# Stepper_Motor_Driver.net
KiCad netlist of a schematic drawn in Altium Designer
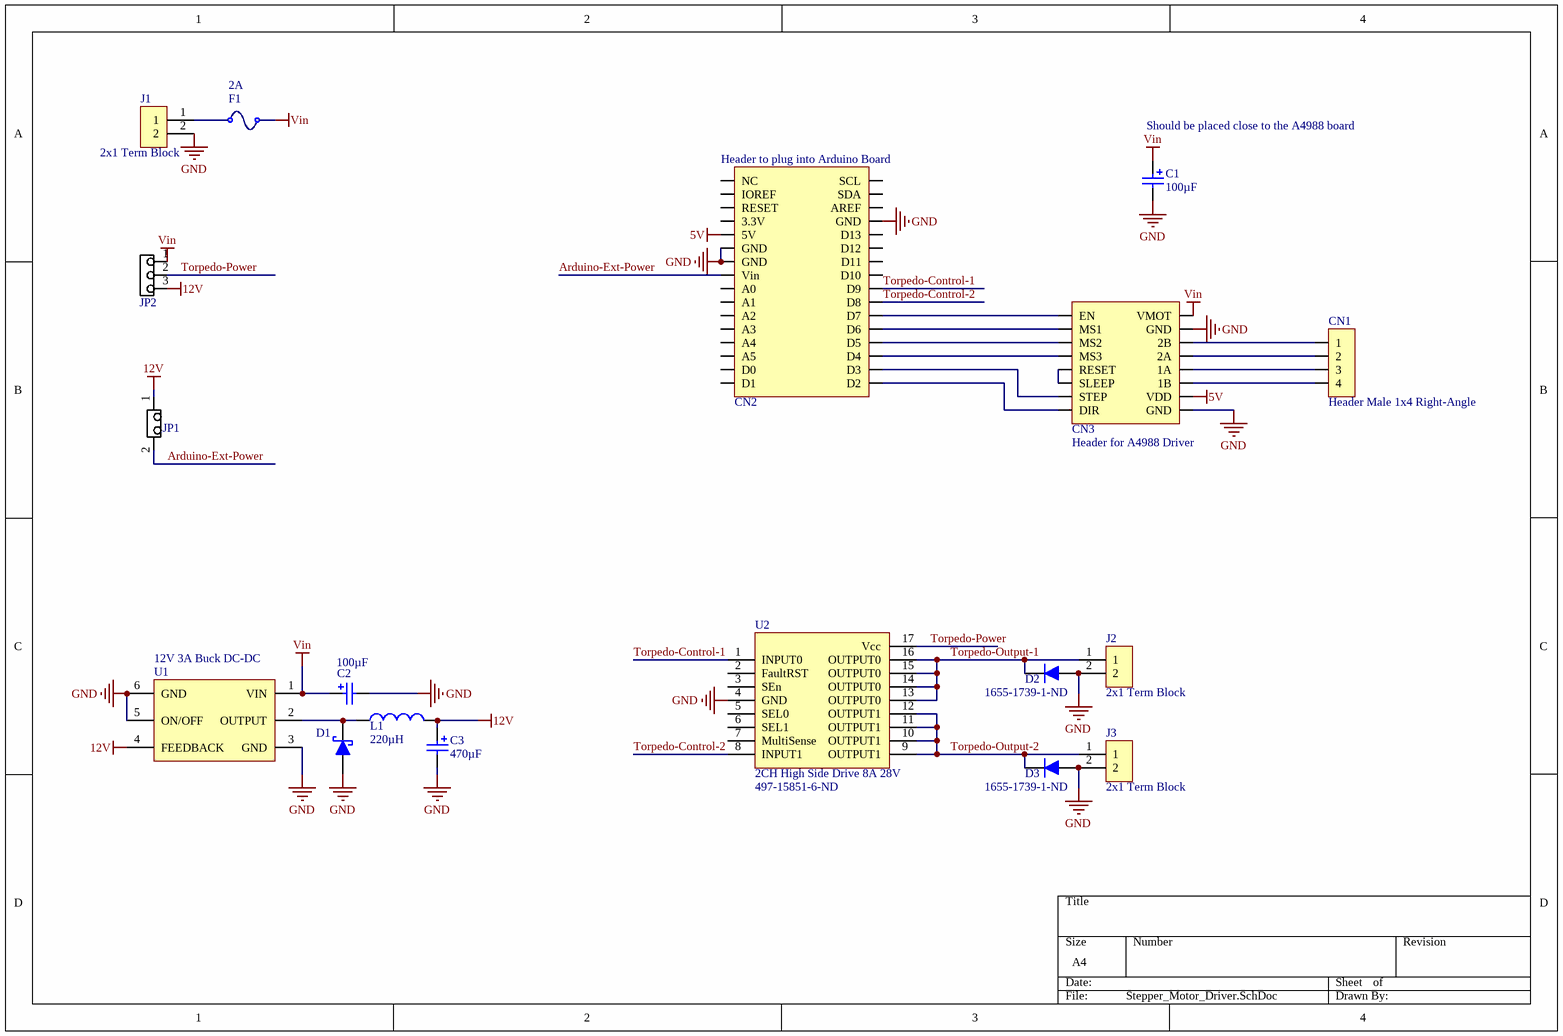
[diagram p0: Stepper_Motor_Driver.SchDoc]

(export (version "E")
  (design (tool "Eeschema 10.0.6"))
  (components
    (comp (ref "C1")
      (value "100µF")
      (footprint "Radial_CAN_6.6mm")
      (description "100µF 35V Aluminum Electrolytic Capacitors Radial, Can - SMD 1000 Hrs @ 105°C")
      (fields (field (name "CREATED BY") "Poorna Chander Kalidas"))
      (libsource (lib "AUVic_Integrated_Library_Capacitors") (part "100uF, 35V, 20%, Alum, SMD"))
    )
    (comp (ref "C2")
      (value "100µF")
      (footprint "Radial_CAN_6.6mm")
      (description "100µF 35V Aluminum Electrolytic Capacitors Radial, Can - SMD 1000 Hrs @ 105°C")
      (fields (field (name "CREATED BY") "Poorna Chander Kalidas"))
      (libsource (lib "AUVic_Integrated_Library_Capacitors") (part "100uF, 35V, 20%, Alum, SMD"))
    )
    (comp (ref "C3")
      (value "470µF")
      (footprint "EEE-1HA221P")
      (description "470µF 25V Aluminum Electrolytic Capacitors Radial, Can - SMD 1000 Hrs @ 105°C")
      (fields (field (name "PUBLISHER") "Poorna Chander Kalidas"))
      (libsource (lib "AUVic_Integrated_Library_Capacitors") (part "470uF 25V SMD Aluminum Nichicon"))
    )
    (comp (ref "CN1")
      (value "Header Male 1x4 Right-Angle")
      (footprint "Header, Male, 1X4, More solder")
      (description "1x4, Pads Pitch: 0.1\" (2.54mm), Right-angle, Through hole")
      (libsource (lib "AUVic_Integrated_Library_Connectors") (part "Header, Male, 1x4, Right-Angle"))
    )
    (comp (ref "CN2")
      (value "Header to plug into Arduino Board")
      (footprint "DIP32 Arduino Shield")
      (libsource (lib "AUVic_Integrated_Library_Connectors") (part "Arduino Shield Heade"))
    )
    (comp (ref "CN3")
      (value "Header for A4988 Driver")
      (footprint "DIP16")
      (description "Header, Female, 2x8, Pitch: 0.1\" (2.54mm),THT")
      (fields (field (name "CREATED BY") "Poorna Chander Kalidas"))
      (libsource (lib "AUVic_Integrated_Library_Connectors") (part "Connector for A4988 Stepper Motor Driver"))
    )
    (comp (ref "D1")
      (value "TSSA5U50E3GCT-ND")
      (footprint "DO-214AC")
      (description "Diode Schottky 50V 5A Surface Mount DO-214AC (SMA)")
      (fields (field (name "CREATED BY") "Poorna Chander Kalidas"))
      (libsource (lib "AUVic_Integrated_Library_Diodes") (part "TSSA5U50E3GCT-ND"))
    )
    (comp (ref "D2")
      (value "JD 2A 600V")
      (footprint "DO-214AA")
      (description "Junction Diode 2A 600V")
      (fields
        (field (name "SUPPLIER PART NUMBER 1") "1655-1739-1-ND")
        (field (name "CREATED BY") "Poorna Chander Kalidas")
        (field (name "PUBLISHER") "AUVic")
      )
      (libsource (lib "AUVic_Integrated_Library_Diodes") (part "JD 2A 600V"))
    )
    (comp (ref "D3")
      (value "JD 2A 600V")
      (footprint "DO-214AA")
      (description "Junction Diode 2A 600V")
      (fields
        (field (name "SUPPLIER PART NUMBER 1") "1655-1739-1-ND")
        (field (name "CREATED BY") "Poorna Chander Kalidas")
        (field (name "PUBLISHER") "AUVic")
      )
      (libsource (lib "AUVic_Integrated_Library_Diodes") (part "JD 2A 600V"))
    )
    (comp (ref "F1")
      (value "2A")
      (footprint "1206 SMD")
      (description "SMD Fuse, 2A, 63V,")
      (fields (field (name "CREATED BY") "Poorna Chander Kalidas"))
      (libsource (lib "AUVic_Integrated_Library_Fuses") (part "SMD Fuse, 2A, 63V,"))
    )
    (comp (ref "J1")
      (value "2x1 Term Block")
      (footprint "2X1 Terminal Blocks")
      (fields (field (name "MADE BY") "Andy Bates"))
      (libsource (lib "AUVic_Integrated_Library_Connectors") (part "2x1 Terminal Block"))
    )
    (comp (ref "J2")
      (value "2x1 Term Block")
      (footprint "2X1 Terminal Blocks")
      (fields (field (name "MADE BY") "Andy Bates"))
      (libsource (lib "") (part "2x1 Terminal Block_1"))
    )
    (comp (ref "J3")
      (value "2x1 Term Block")
      (footprint "2X1 Terminal Blocks")
      (fields (field (name "MADE BY") "Andy Bates"))
      (libsource (lib "") (part "2x1 Terminal Block_1"))
    )
    (comp (ref "JP1")
      (value "1X2 Pin Head")
      (footprint "2X1 Males Header")
      (fields (field (name "MADE BY") "Andy Bates"))
      (libsource (lib "AUVic_Integrated_Library_Connectors") (part "1x2 Male Header"))
    )
    (comp (ref "JP2")
      (value "1x3 Male Jumper")
      (footprint "Header, Male, 1x3, Pitch: 0.1\" (2.54mm),THT")
      (fields (field (name "MADE BY") "Poorna Chander Kalidas"))
      (libsource (lib "AUVic_Integrated_Library_Connectors") (part "1x3 Male Jumper"))
    )
    (comp (ref "L1")
      (value "220µH")
      (footprint "Inductor Cylinder - 1422435C")
      (description "220µH Unshielded Wirewound Inductor 3.5A 96 mOhm Max Radial")
      (fields (field (name "CREATED BY") "Poorna Chander Kalidas"))
      (libsource (lib "AUVic_Integrated_Library_Inductors") (part "220µH 3.5A Inductor"))
    )
    (comp (ref "U1")
      (value "12V 3A Buck DC-DC")
      (footprint "5-DDPAK")
      (fields (field (name "CREATED BY") "Poorna Chander Kalidas"))
      (libsource (lib "AUVic_Integrated_Library_Regulators") (part "12V 3A Buck DC-DC"))
    )
    (comp (ref "U2")
      (value "2CH High Side Drive 8A 28V")
      (footprint "SSOP50P600X170_HS-17N")
      (description "2 Channel High Side Drive MOSFET controlable by logic signal")
      (fields (field (name "SUPPLIER PART NUMBER 1") "497-15851-6-ND"))
      (libsource (lib "AUVic_Integrated_Library_Transistors") (part "2CH High Side Drive w/ Logic Signal 8A 28V"))
    )
  )
  (nets
    (net (code "1") (name "/Arduino-Ext-Power") (class "Default")
      (node (ref "CN2") (pin "8") (pinfunction "Vin_8") (pintype "passive"))
      (node (ref "JP1") (pin "2") (pinfunction "2_2") (pintype "passive"))
    )
    (net (code "2") (name "/Torpedo-Control-1") (class "Default")
      (node (ref "CN2") (pin "24") (pinfunction "D9_24") (pintype "passive"))
      (node (ref "U2") (pin "1") (pinfunction "INPUT0_1") (pintype "passive"))
    )
    (net (code "3") (name "/Torpedo-Control-2") (class "Default")
      (node (ref "CN2") (pin "23") (pinfunction "D8_23") (pintype "passive"))
      (node (ref "U2") (pin "8") (pinfunction "INPUT1_8") (pintype "passive"))
    )
    (net (code "4") (name "/Torpedo-Output-1") (class "Default")
      (node (ref "D2") (pin "K") (pinfunction "Cathode_K") (pintype "passive"))
      (node (ref "J2") (pin "1") (pinfunction "1_1") (pintype "passive"))
      (node (ref "U2") (pin "13") (pinfunction "OUTPUT0_13") (pintype "passive"))
      (node (ref "U2") (pin "14") (pinfunction "OUTPUT0_14") (pintype "passive"))
      (node (ref "U2") (pin "15") (pinfunction "OUTPUT0_15") (pintype "passive"))
      (node (ref "U2") (pin "16") (pinfunction "OUTPUT0_16") (pintype "passive"))
    )
    (net (code "5") (name "/Torpedo-Output-2") (class "Default")
      (node (ref "D3") (pin "K") (pinfunction "Cathode_K") (pintype "passive"))
      (node (ref "J3") (pin "1") (pinfunction "1_1") (pintype "passive"))
      (node (ref "U2") (pin "10") (pinfunction "OUTPUT1_10") (pintype "passive"))
      (node (ref "U2") (pin "11") (pinfunction "OUTPUT1_11") (pintype "passive"))
      (node (ref "U2") (pin "12") (pinfunction "OUTPUT1_12") (pintype "passive"))
      (node (ref "U2") (pin "9") (pinfunction "OUTPUT1_9") (pintype "passive"))
    )
    (net (code "6") (name "/Torpedo-Power") (class "Default")
      (node (ref "JP2") (pin "2") (pinfunction "2_2") (pintype "passive"))
      (node (ref "U2") (pin "17") (pinfunction "Vcc_17") (pintype "passive"))
    )
    (net (code "7") (name "5V") (class "Default")
      (node (ref "CN2") (pin "5") (pinfunction "5V_5") (pintype "passive"))
      (node (ref "CN3") (pin "10") (pinfunction "VDD_10") (pintype "passive"))
    )
    (net (code "8") (name "12V") (class "Default")
      (node (ref "C3") (pin "1") (pinfunction "Anode_1") (pintype "passive"))
      (node (ref "JP1") (pin "1") (pinfunction "1_1") (pintype "passive"))
      (node (ref "JP2") (pin "3") (pinfunction "3_3") (pintype "passive"))
      (node (ref "L1") (pin "2") (pinfunction "2_2") (pintype "passive"))
      (node (ref "U1") (pin "4") (pinfunction "FEEDBACK_4") (pintype "passive"))
    )
    (net (code "9") (name "GND") (class "Default")
      (node (ref "C1") (pin "2") (pinfunction "Cathode_2") (pintype "passive"))
      (node (ref "C2") (pin "2") (pinfunction "Cathode_2") (pintype "passive"))
      (node (ref "C3") (pin "2") (pinfunction "Cathode_2") (pintype "passive"))
      (node (ref "CN2") (pin "29") (pinfunction "GND_29") (pintype "passive"))
      (node (ref "CN2") (pin "6") (pinfunction "GND_6") (pintype "passive"))
      (node (ref "CN2") (pin "7") (pinfunction "GND_7") (pintype "passive"))
      (node (ref "CN3") (pin "15") (pinfunction "GND_15") (pintype "passive"))
      (node (ref "CN3") (pin "9") (pinfunction "GND_9") (pintype "passive"))
      (node (ref "D1") (pin "1") (pinfunction "Anode_1") (pintype "passive"))
      (node (ref "D2") (pin "A") (pinfunction "Anode_A") (pintype "passive"))
      (node (ref "D3") (pin "A") (pinfunction "Anode_A") (pintype "passive"))
      (node (ref "J1") (pin "2") (pinfunction "2_2") (pintype "passive"))
      (node (ref "J2") (pin "2") (pinfunction "2_2") (pintype "passive"))
      (node (ref "J3") (pin "2") (pinfunction "2_2") (pintype "passive"))
      (node (ref "U1") (pin "3") (pinfunction "GND_3") (pintype "passive"))
      (node (ref "U1") (pin "5") (pinfunction "ON/OFF_5") (pintype "passive"))
      (node (ref "U1") (pin "6") (pinfunction "GND_6") (pintype "passive"))
      (node (ref "U2") (pin "4") (pinfunction "GND_4") (pintype "passive"))
    )
    (net (code "10") (name "Net-(CN2-D2)") (class "Default")
      (node (ref "CN2") (pin "17") (pinfunction "D2_17") (pintype "passive"))
      (node (ref "CN3") (pin "8") (pinfunction "DIR_8") (pintype "passive"))
    )
    (net (code "11") (name "Net-(CN2-D3)") (class "Default")
      (node (ref "CN2") (pin "18") (pinfunction "D3_18") (pintype "passive"))
      (node (ref "CN3") (pin "7") (pinfunction "STEP_7") (pintype "passive"))
    )
    (net (code "12") (name "Net-(CN2-D4)") (class "Default")
      (node (ref "CN2") (pin "19") (pinfunction "D4_19") (pintype "passive"))
      (node (ref "CN3") (pin "4") (pinfunction "MS3_4") (pintype "passive"))
    )
    (net (code "13") (name "Net-(CN2-D5)") (class "Default")
      (node (ref "CN2") (pin "20") (pinfunction "D5_20") (pintype "passive"))
      (node (ref "CN3") (pin "3") (pinfunction "MS2_3") (pintype "passive"))
    )
    (net (code "14") (name "Net-(CN2-D6)") (class "Default")
      (node (ref "CN2") (pin "21") (pinfunction "D6_21") (pintype "passive"))
      (node (ref "CN3") (pin "2") (pinfunction "MS1_2") (pintype "passive"))
    )
    (net (code "15") (name "Net-(CN2-D7)") (class "Default")
      (node (ref "CN2") (pin "22") (pinfunction "D7_22") (pintype "passive"))
      (node (ref "CN3") (pin "1") (pinfunction "EN_1") (pintype "passive"))
    )
    (net (code "16") (name "Net-(CN3-1A)") (class "Default")
      (node (ref "CN1") (pin "3") (pinfunction "3_3") (pintype "passive"))
      (node (ref "CN3") (pin "12") (pinfunction "1A_12") (pintype "passive"))
    )
    (net (code "17") (name "Net-(CN3-1B)") (class "Default")
      (node (ref "CN1") (pin "4") (pinfunction "4_4") (pintype "passive"))
      (node (ref "CN3") (pin "11") (pinfunction "1B_11") (pintype "passive"))
    )
    (net (code "18") (name "Net-(CN3-2A)") (class "Default")
      (node (ref "CN1") (pin "2") (pinfunction "2_2") (pintype "passive"))
      (node (ref "CN3") (pin "13") (pinfunction "2A_13") (pintype "passive"))
    )
    (net (code "19") (name "Net-(CN3-2B)") (class "Default")
      (node (ref "CN1") (pin "1") (pinfunction "1_1") (pintype "passive"))
      (node (ref "CN3") (pin "14") (pinfunction "2B_14") (pintype "passive"))
    )
    (net (code "20") (name "Net-(CN3-RESET)") (class "Default")
      (node (ref "CN3") (pin "5") (pinfunction "RESET_5") (pintype "passive"))
      (node (ref "CN3") (pin "6") (pinfunction "SLEEP_6") (pintype "passive"))
    )
    (net (code "21") (name "Net-(D1-Cathode)") (class "Default")
      (node (ref "D1") (pin "2") (pinfunction "Cathode_2") (pintype "passive"))
      (node (ref "L1") (pin "1") (pinfunction "1_1") (pintype "passive"))
      (node (ref "U1") (pin "2") (pinfunction "OUTPUT_2") (pintype "passive"))
    )
    (net (code "22") (name "Net-(F1-Pad1)") (class "Default")
      (node (ref "F1") (pin "1") (pinfunction "1_1") (pintype "passive"))
      (node (ref "J1") (pin "1") (pinfunction "1_1") (pintype "passive"))
    )
    (net (code "23") (name "Vin") (class "Default")
      (node (ref "C1") (pin "1") (pinfunction "Anode_1") (pintype "passive"))
      (node (ref "C2") (pin "1") (pinfunction "Anode_1") (pintype "passive"))
      (node (ref "CN3") (pin "16") (pinfunction "VMOT_16") (pintype "passive"))
      (node (ref "F1") (pin "2") (pinfunction "2_2") (pintype "passive"))
      (node (ref "JP2") (pin "1") (pinfunction "1_1") (pintype "passive"))
      (node (ref "U1") (pin "1") (pinfunction "VIN_1") (pintype "passive"))
    )
    (net (code "24") (name "unconnected-(CN2-3.3V-Pad4)") (class "Default")
      (node (ref "CN2") (pin "4") (pinfunction "3.3V_4") (pintype "passive"))
    )
    (net (code "25") (name "unconnected-(CN2-A0-Pad9)") (class "Default")
      (node (ref "CN2") (pin "9") (pinfunction "A0_9") (pintype "passive"))
    )
    (net (code "26") (name "unconnected-(CN2-A1-Pad10)") (class "Default")
      (node (ref "CN2") (pin "10") (pinfunction "A1_10") (pintype "passive"))
    )
    (net (code "27") (name "unconnected-(CN2-A2-Pad11)") (class "Default")
      (node (ref "CN2") (pin "11") (pinfunction "A2_11") (pintype "passive"))
    )
    (net (code "28") (name "unconnected-(CN2-A3-Pad12)") (class "Default")
      (node (ref "CN2") (pin "12") (pinfunction "A3_12") (pintype "passive"))
    )
    (net (code "29") (name "unconnected-(CN2-A4-Pad13)") (class "Default")
      (node (ref "CN2") (pin "13") (pinfunction "A4_13") (pintype "passive"))
    )
    (net (code "30") (name "unconnected-(CN2-A5-Pad14)") (class "Default")
      (node (ref "CN2") (pin "14") (pinfunction "A5_14") (pintype "passive"))
    )
    (net (code "31") (name "unconnected-(CN2-AREF-Pad30)") (class "Default")
      (node (ref "CN2") (pin "30") (pinfunction "AREF_30") (pintype "passive"))
    )
    (net (code "32") (name "unconnected-(CN2-D0-Pad15)") (class "Default")
      (node (ref "CN2") (pin "15") (pinfunction "D0_15") (pintype "passive"))
    )
    (net (code "33") (name "unconnected-(CN2-D1-Pad16)") (class "Default")
      (node (ref "CN2") (pin "16") (pinfunction "D1_16") (pintype "passive"))
    )
    (net (code "34") (name "unconnected-(CN2-D10-Pad25)") (class "Default")
      (node (ref "CN2") (pin "25") (pinfunction "D10_25") (pintype "passive"))
    )
    (net (code "35") (name "unconnected-(CN2-D11-Pad26)") (class "Default")
      (node (ref "CN2") (pin "26") (pinfunction "D11_26") (pintype "passive"))
    )
    (net (code "36") (name "unconnected-(CN2-D12-Pad27)") (class "Default")
      (node (ref "CN2") (pin "27") (pinfunction "D12_27") (pintype "passive"))
    )
    (net (code "37") (name "unconnected-(CN2-D13-Pad28)") (class "Default")
      (node (ref "CN2") (pin "28") (pinfunction "D13_28") (pintype "passive"))
    )
    (net (code "38") (name "unconnected-(CN2-IOREF-Pad2)") (class "Default")
      (node (ref "CN2") (pin "2") (pinfunction "IOREF_2") (pintype "passive"))
    )
    (net (code "39") (name "unconnected-(CN2-NC-Pad1)") (class "Default")
      (node (ref "CN2") (pin "1") (pinfunction "NC_1") (pintype "passive"))
    )
    (net (code "40") (name "unconnected-(CN2-RESET-Pad3)") (class "Default")
      (node (ref "CN2") (pin "3") (pinfunction "RESET_3") (pintype "passive"))
    )
    (net (code "41") (name "unconnected-(CN2-SCL-Pad32)") (class "Default")
      (node (ref "CN2") (pin "32") (pinfunction "SCL_32") (pintype "passive"))
    )
    (net (code "42") (name "unconnected-(CN2-SDA-Pad31)") (class "Default")
      (node (ref "CN2") (pin "31") (pinfunction "SDA_31") (pintype "passive"))
    )
    (net (code "43") (name "unconnected-(U2-FaultRST-Pad2)") (class "Default")
      (node (ref "U2") (pin "2") (pinfunction "FaultRST_2") (pintype "passive"))
    )
    (net (code "44") (name "unconnected-(U2-MultiSense-Pad7)") (class "Default")
      (node (ref "U2") (pin "7") (pinfunction "MultiSense_7") (pintype "passive"))
    )
    (net (code "45") (name "unconnected-(U2-SEL0-Pad5)") (class "Default")
      (node (ref "U2") (pin "5") (pinfunction "SEL0_5") (pintype "passive"))
    )
    (net (code "46") (name "unconnected-(U2-SEL1-Pad6)") (class "Default")
      (node (ref "U2") (pin "6") (pinfunction "SEL1_6") (pintype "passive"))
    )
    (net (code "47") (name "unconnected-(U2-SEn-Pad3)") (class "Default")
      (node (ref "U2") (pin "3") (pinfunction "SEn_3") (pintype "passive"))
    )
  )
)
